# DC_POWER.net
KiCad netlist of a schematic drawn in Altium Designer
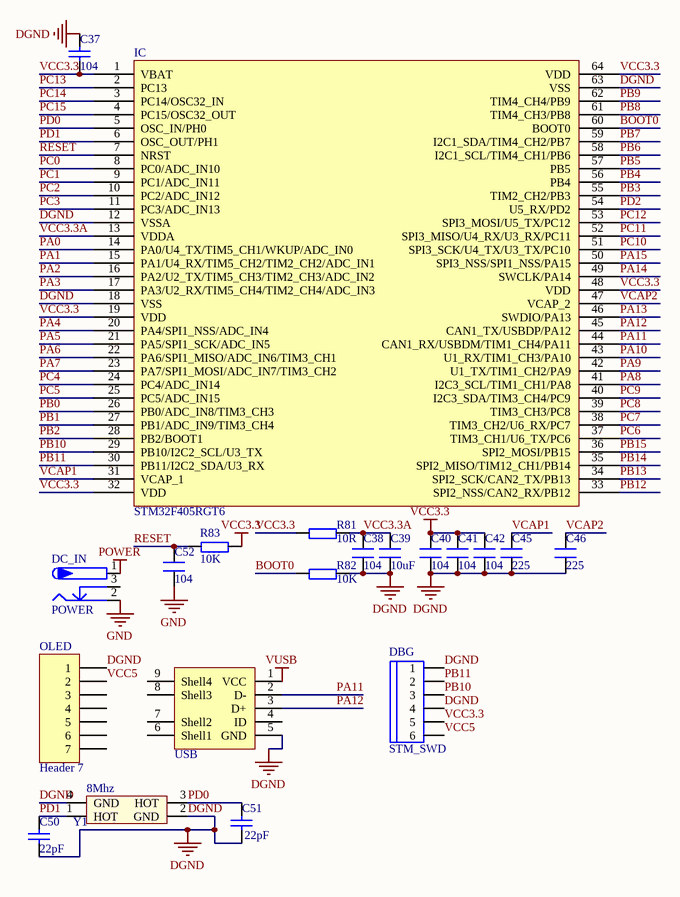
[diagram p0: DC_POWER.SchDoc]

(export (version "E")
  (design (tool "Eeschema 10.0.6"))
  (components
    (comp (ref "C37") (value "104") (footprint "C 0603_L") (libsource (lib "L476") (part "CAP")))
    (comp (ref "C38")
      (value "104")
      (footprint "C 0603_L")
      (libsource (lib "WarShip V3 STM32103封装库") (part "C"))
    )
    (comp (ref "C39")
      (value "10uF")
      (footprint "C 0603_L")
      (libsource (lib "WarShip V3 STM32103封装库") (part "C"))
    )
    (comp (ref "C40")
      (value "104")
      (footprint "C 0603_L")
      (libsource (lib "WarShip V3 STM32103封装库") (part "C"))
    )
    (comp (ref "C41")
      (value "104")
      (footprint "C 0603_L")
      (libsource (lib "WarShip V3 STM32103封装库") (part "C"))
    )
    (comp (ref "C42")
      (value "104")
      (footprint "C 0603_L")
      (libsource (lib "WarShip V3 STM32103封装库") (part "C"))
    )
    (comp (ref "C45")
      (value "225")
      (footprint "C 0603_L")
      (libsource (lib "WarShip V3 STM32103封装库") (part "C"))
    )
    (comp (ref "C46")
      (value "225")
      (footprint "C 0603_L")
      (libsource (lib "WarShip V3 STM32103封装库") (part "C"))
    )
    (comp (ref "C50") (value "22pF") (footprint "C 0603_L") (libsource (lib "L476") (part "CAP")))
    (comp (ref "C51") (value "22pF") (footprint "C 0603_L") (libsource (lib "L476") (part "CAP")))
    (comp (ref "C52")
      (value "104")
      (footprint "C 0603_L")
      (libsource (lib "WarShip V3 STM32103封装库") (part "C"))
    )
    (comp (ref "DBG") (value "STM_SWD") (footprint "SH1.0_6P") (libsource (lib "MiniFly ") (part "HEAD6")))
    (comp (ref "DC_IN")
      (value "POWER")
      (footprint "DC10B")
      (description "低压电源接口")
      (fields (field (name "版权归属") "源创客"))
      (libsource (lib "IMX6UL_ALPHA(底板)_V2.0") (part "P-DC"))
    )
    (comp (ref "IC")
      (value "STM32F405RGT6")
      (footprint "LQFP64 10X10_L")
      (description "Flaah:256/RAM:48/IO:51")
      (libsource (lib "ATKF405 V1.1") (part "STM32F405RGT6"))
    )
    (comp (ref "OLED")
      (value "Header 7")
      (footprint "HDR2.54-M-LI-7P")
      (description "Header, 7-Pin")
      (fields (field (name "PUBLISHER") "Altium Limited"))
      (libsource (lib "Miscellaneous Connectors") (part "Header 7"))
    )
    (comp (ref "R81")
      (value "10R")
      (footprint "R 0603_L")
      (libsource (lib "WarShip V3 STM32103封装库") (part "R"))
    )
    (comp (ref "R82")
      (value "10K")
      (footprint "R 0603_L")
      (libsource (lib "WarShip V3 STM32103封装库") (part "R"))
    )
    (comp (ref "R83")
      (value "10K")
      (footprint "R 0603_L")
      (libsource (lib "WarShip V3 STM32103封装库") (part "R"))
    )
    (comp (ref "USB")
      (value "MICRO-USB")
      (footprint "USB-AB-5S")
      (description "Micro USB 5.9有柱脚长1.25加长针")
      (libsource (lib "Pandora_STM32L4_Board_V2.4") (part "J-MICRO-USB-5S"))
    )
    (comp (ref "Y1")
      (value "8Mhz")
      (footprint "XTAL-3225")
      (description "3225贴片无源晶振")
      (libsource (lib "ALIENTEK_COMPONENT") (part "XTAL_3225"))
    )
  )
  (nets
    (net (code "1") (name "/BOOT0") (class "Default")
      (node (ref "IC") (pin "60") (pinfunction "BOOT0_60") (pintype "passive"))
      (node (ref "R82") (pin "1") (pintype "passive"))
    )
    (net (code "2") (name "/PA0") (class "Default")
      (node (ref "IC") (pin "14") (pinfunction "PA0/U4_TX/TIM5_CH1/WKUP/ADC_IN0_14") (pintype "passive"))
    )
    (net (code "3") (name "/PA1") (class "Default")
      (node (ref "IC") (pin "15") (pinfunction "PA1/U4_RX/TIM5_CH2/TIM2_CH2/ADC_IN1_15") (pintype "passive"))
    )
    (net (code "4") (name "/PA2") (class "Default")
      (node (ref "IC") (pin "16") (pinfunction "PA2/U2_TX/TIM5_CH3/TIM2_CH3/ADC_IN2_16") (pintype "passive"))
    )
    (net (code "5") (name "/PA3") (class "Default")
      (node (ref "IC") (pin "17") (pinfunction "PA3/U2_RX/TIM5_CH4/TIM2_CH4/ADC_IN3_17") (pintype "passive"))
    )
    (net (code "6") (name "/PA4") (class "Default")
      (node (ref "IC") (pin "20") (pinfunction "PA4/SPI1_NSS/ADC_IN4_20") (pintype "passive"))
    )
    (net (code "7") (name "/PA5") (class "Default")
      (node (ref "IC") (pin "21") (pinfunction "PA5/SPI1_SCK/ADC_IN5_21") (pintype "passive"))
    )
    (net (code "8") (name "/PA6") (class "Default")
      (node (ref "IC") (pin "22") (pinfunction "PA6/SPI1_MISO/ADC_IN6/TIM3_CH1_22") (pintype "passive"))
    )
    (net (code "9") (name "/PA7") (class "Default")
      (node (ref "IC") (pin "23") (pinfunction "PA7/SPI1_MOSI/ADC_IN7/TIM3_CH2_23") (pintype "passive"))
    )
    (net (code "10") (name "/PA8") (class "Default")
      (node (ref "IC") (pin "41") (pinfunction "I2C3_SCL/TIM1_CH1/PA8_41") (pintype "passive"))
    )
    (net (code "11") (name "/PA9") (class "Default")
      (node (ref "IC") (pin "42") (pinfunction "U1_TX/TIM1_CH2/PA9_42") (pintype "passive"))
    )
    (net (code "12") (name "/PA10") (class "Default")
      (node (ref "IC") (pin "43") (pinfunction "U1_RX/TIM1_CH3/PA10_43") (pintype "passive"))
    )
    (net (code "13") (name "/PA11") (class "Default")
      (node (ref "IC") (pin "44") (pinfunction "CAN1_RX/USBDM/TIM1_CH4/PA11_44") (pintype "passive"))
      (node (ref "USB") (pin "2") (pinfunction "D-_2") (pintype "passive"))
    )
    (net (code "14") (name "/PA12") (class "Default")
      (node (ref "IC") (pin "45") (pinfunction "CAN1_TX/USBDP/PA12_45") (pintype "passive"))
      (node (ref "USB") (pin "3") (pinfunction "D+_3") (pintype "passive"))
    )
    (net (code "15") (name "/PA13") (class "Default")
      (node (ref "IC") (pin "46") (pinfunction "SWDIO/PA13_46") (pintype "passive"))
    )
    (net (code "16") (name "/PA14") (class "Default")
      (node (ref "IC") (pin "49") (pinfunction "SWCLK/PA14_49") (pintype "passive"))
    )
    (net (code "17") (name "/PA15") (class "Default")
      (node (ref "IC") (pin "50") (pinfunction "SPI3_NSS/SPI1_NSS/PA15_50") (pintype "passive"))
    )
    (net (code "18") (name "/PB0") (class "Default")
      (node (ref "IC") (pin "26") (pinfunction "PB0/ADC_IN8/TIM3_CH3_26") (pintype "passive"))
    )
    (net (code "19") (name "/PB1") (class "Default")
      (node (ref "IC") (pin "27") (pinfunction "PB1/ADC_IN9/TIM3_CH4_27") (pintype "passive"))
    )
    (net (code "20") (name "/PB2") (class "Default")
      (node (ref "IC") (pin "28") (pinfunction "PB2/BOOT1_28") (pintype "passive"))
    )
    (net (code "21") (name "/PB3") (class "Default")
      (node (ref "IC") (pin "55") (pinfunction "TIM2_CH2/PB3_55") (pintype "passive"))
    )
    (net (code "22") (name "/PB4") (class "Default")
      (node (ref "IC") (pin "56") (pinfunction "PB4_56") (pintype "passive"))
    )
    (net (code "23") (name "/PB5") (class "Default")
      (node (ref "IC") (pin "57") (pinfunction "PB5_57") (pintype "passive"))
    )
    (net (code "24") (name "/PB6") (class "Default")
      (node (ref "IC") (pin "58") (pinfunction "I2C1_SCL/TIM4_CH1/PB6_58") (pintype "passive"))
    )
    (net (code "25") (name "/PB7") (class "Default")
      (node (ref "IC") (pin "59") (pinfunction "I2C1_SDA/TIM4_CH2/PB7_59") (pintype "passive"))
    )
    (net (code "26") (name "/PB8") (class "Default")
      (node (ref "IC") (pin "61") (pinfunction "TIM4_CH3/PB8_61") (pintype "passive"))
    )
    (net (code "27") (name "/PB9") (class "Default")
      (node (ref "IC") (pin "62") (pinfunction "TIM4_CH4/PB9_62") (pintype "passive"))
    )
    (net (code "28") (name "/PB10") (class "Default")
      (node (ref "DBG") (pin "3") (pinfunction "3_3") (pintype "passive"))
      (node (ref "IC") (pin "29") (pinfunction "PB10/I2C2_SCL/U3_TX_29") (pintype "passive"))
    )
    (net (code "29") (name "/PB11") (class "Default")
      (node (ref "DBG") (pin "2") (pinfunction "2_2") (pintype "passive"))
      (node (ref "IC") (pin "30") (pinfunction "PB11/I2C2_SDA/U3_RX_30") (pintype "passive"))
    )
    (net (code "30") (name "/PB12") (class "Default")
      (node (ref "IC") (pin "33") (pinfunction "SPI2_NSS/CAN2_RX/PB12_33") (pintype "passive"))
    )
    (net (code "31") (name "/PB13") (class "Default")
      (node (ref "IC") (pin "34") (pinfunction "SPI2_SCK/CAN2_TX/PB13_34") (pintype "passive"))
    )
    (net (code "32") (name "/PB14") (class "Default")
      (node (ref "IC") (pin "35") (pinfunction "SPI2_MISO/TIM12_CH1/PB14_35") (pintype "passive"))
    )
    (net (code "33") (name "/PB15") (class "Default")
      (node (ref "IC") (pin "36") (pinfunction "SPI2_MOSI/PB15_36") (pintype "passive"))
    )
    (net (code "34") (name "/PC0") (class "Default")
      (node (ref "IC") (pin "8") (pinfunction "PC0/ADC_IN10_8") (pintype "passive"))
    )
    (net (code "35") (name "/PC1") (class "Default")
      (node (ref "IC") (pin "9") (pinfunction "PC1/ADC_IN11_9") (pintype "passive"))
    )
    (net (code "36") (name "/PC2") (class "Default")
      (node (ref "IC") (pin "10") (pinfunction "PC2/ADC_IN12_10") (pintype "passive"))
    )
    (net (code "37") (name "/PC3") (class "Default")
      (node (ref "IC") (pin "11") (pinfunction "PC3/ADC_IN13_11") (pintype "passive"))
    )
    (net (code "38") (name "/PC4") (class "Default")
      (node (ref "IC") (pin "24") (pinfunction "PC4/ADC_IN14_24") (pintype "passive"))
    )
    (net (code "39") (name "/PC5") (class "Default")
      (node (ref "IC") (pin "25") (pinfunction "PC5/ADC_IN15_25") (pintype "passive"))
    )
    (net (code "40") (name "/PC6") (class "Default")
      (node (ref "IC") (pin "37") (pinfunction "TIM3_CH1/U6_TX/PC6_37") (pintype "passive"))
    )
    (net (code "41") (name "/PC7") (class "Default")
      (node (ref "IC") (pin "38") (pinfunction "TIM3_CH2/U6_RX/PC7_38") (pintype "passive"))
    )
    (net (code "42") (name "/PC8") (class "Default")
      (node (ref "IC") (pin "39") (pinfunction "TIM3_CH3/PC8_39") (pintype "passive"))
    )
    (net (code "43") (name "/PC9") (class "Default")
      (node (ref "IC") (pin "40") (pinfunction "I2C3_SDA/TIM3_CH4/PC9_40") (pintype "passive"))
    )
    (net (code "44") (name "/PC10") (class "Default")
      (node (ref "IC") (pin "51") (pinfunction "SPI3_SCK/U4_TX/U3_TX/PC10_51") (pintype "passive"))
    )
    (net (code "45") (name "/PC11") (class "Default")
      (node (ref "IC") (pin "52") (pinfunction "SPI3_MISO/U4_RX/U3_RX/PC11_52") (pintype "passive"))
    )
    (net (code "46") (name "/PC12") (class "Default")
      (node (ref "IC") (pin "53") (pinfunction "SPI3_MOSI/U5_TX/PC12_53") (pintype "passive"))
    )
    (net (code "47") (name "/PC13") (class "Default")
      (node (ref "IC") (pin "2") (pinfunction "PC13_2") (pintype "passive"))
    )
    (net (code "48") (name "/PC14") (class "Default")
      (node (ref "IC") (pin "3") (pinfunction "PC14/OSC32_IN_3") (pintype "passive"))
    )
    (net (code "49") (name "/PC15") (class "Default")
      (node (ref "IC") (pin "4") (pinfunction "PC15/OSC32_OUT_4") (pintype "passive"))
    )
    (net (code "50") (name "/PD0") (class "Default")
      (node (ref "C51") (pin "2") (pinfunction "2_2") (pintype "passive"))
      (node (ref "IC") (pin "5") (pinfunction "OSC_IN/PH0_5") (pintype "passive"))
      (node (ref "Y1") (pin "3") (pinfunction "HOT_3") (pintype "passive"))
    )
    (net (code "51") (name "/PD1") (class "Default")
      (node (ref "C50") (pin "2") (pinfunction "2_2") (pintype "passive"))
      (node (ref "IC") (pin "6") (pinfunction "OSC_OUT/PH1_6") (pintype "passive"))
      (node (ref "Y1") (pin "1") (pinfunction "HOT_1") (pintype "passive"))
    )
    (net (code "52") (name "/PD2") (class "Default")
      (node (ref "IC") (pin "54") (pinfunction "U5_RX/PD2_54") (pintype "passive"))
    )
    (net (code "53") (name "/RESET") (class "Default")
      (node (ref "C52") (pin "2") (pintype "passive"))
      (node (ref "IC") (pin "7") (pinfunction "NRST_7") (pintype "passive"))
      (node (ref "R83") (pin "1") (pintype "passive"))
    )
    (net (code "54") (name "/VCAP1") (class "Default")
      (node (ref "C45") (pin "2") (pintype "passive"))
      (node (ref "IC") (pin "31") (pinfunction "VCAP_1_31") (pintype "passive"))
    )
    (net (code "55") (name "/VCAP2") (class "Default")
      (node (ref "C46") (pin "2") (pintype "passive"))
      (node (ref "IC") (pin "47") (pinfunction "VCAP_2_47") (pintype "passive"))
    )
    (net (code "56") (name "/VCC3.3A") (class "Default")
      (node (ref "C38") (pin "2") (pintype "passive"))
      (node (ref "C39") (pin "2") (pintype "passive"))
      (node (ref "IC") (pin "13") (pinfunction "VDDA_13") (pintype "passive"))
      (node (ref "R81") (pin "2") (pintype "passive"))
    )
    (net (code "57") (name "/VCC5") (class "Default")
      (node (ref "DBG") (pin "6") (pinfunction "6_6") (pintype "passive"))
      (node (ref "OLED") (pin "2") (pinfunction "2_2") (pintype "passive"))
    )
    (net (code "58") (name "DGND") (class "Default")
      (node (ref "C37") (pin "1") (pinfunction "1_1") (pintype "passive"))
      (node (ref "C38") (pin "1") (pintype "passive"))
      (node (ref "C39") (pin "1") (pintype "passive"))
      (node (ref "C40") (pin "1") (pintype "passive"))
      (node (ref "C41") (pin "1") (pintype "passive"))
      (node (ref "C42") (pin "1") (pintype "passive"))
      (node (ref "C45") (pin "1") (pintype "passive"))
      (node (ref "C46") (pin "1") (pintype "passive"))
      (node (ref "C50") (pin "1") (pinfunction "1_1") (pintype "passive"))
      (node (ref "C51") (pin "1") (pinfunction "1_1") (pintype "passive"))
      (node (ref "DBG") (pin "1") (pinfunction "1_1") (pintype "passive"))
      (node (ref "DBG") (pin "4") (pinfunction "4_4") (pintype "passive"))
      (node (ref "IC") (pin "12") (pinfunction "VSSA_12") (pintype "passive"))
      (node (ref "IC") (pin "18") (pinfunction "VSS_18") (pintype "passive"))
      (node (ref "IC") (pin "63") (pinfunction "VSS_63") (pintype "passive"))
      (node (ref "OLED") (pin "1") (pinfunction "1_1") (pintype "passive"))
      (node (ref "R82") (pin "2") (pintype "passive"))
      (node (ref "USB") (pin "5") (pinfunction "GND_5") (pintype "passive"))
      (node (ref "Y1") (pin "2") (pinfunction "GND_2") (pintype "passive"))
      (node (ref "Y1") (pin "4") (pinfunction "GND_4") (pintype "passive"))
    )
    (net (code "59") (name "GND") (class "Default")
      (node (ref "C52") (pin "1") (pintype "passive"))
      (node (ref "DC_IN") (pin "2") (pintype "power_in"))
    )
    (net (code "60") (name "POWER") (class "Default") (node (ref "DC_IN") (pin "1") (pintype "power_in")))
    (net (code "61") (name "VCC3.3") (class "Default")
      (node (ref "C37") (pin "2") (pinfunction "2_2") (pintype "passive"))
      (node (ref "C40") (pin "2") (pintype "passive"))
      (node (ref "C41") (pin "2") (pintype "passive"))
      (node (ref "C42") (pin "2") (pintype "passive"))
      (node (ref "DBG") (pin "5") (pinfunction "5_5") (pintype "passive"))
      (node (ref "IC") (pin "1") (pinfunction "VBAT_1") (pintype "passive"))
      (node (ref "IC") (pin "19") (pinfunction "VDD_19") (pintype "passive"))
      (node (ref "IC") (pin "32") (pinfunction "VDD_32") (pintype "passive"))
      (node (ref "IC") (pin "48") (pinfunction "VDD_48") (pintype "passive"))
      (node (ref "IC") (pin "64") (pinfunction "VDD_64") (pintype "passive"))
      (node (ref "R81") (pin "1") (pintype "passive"))
      (node (ref "R83") (pin "2") (pintype "passive"))
    )
    (net (code "62") (name "VUSB") (class "Default")
      (node (ref "USB") (pin "1") (pinfunction "VCC_1") (pintype "passive"))
    )
    (net (code "63") (name "unconnected-(DC_IN-Pad3)") (class "Default")
      (node (ref "DC_IN") (pin "3") (pintype "power_in"))
    )
    (net (code "64") (name "unconnected-(OLED-Pad3)") (class "Default")
      (node (ref "OLED") (pin "3") (pinfunction "3_3") (pintype "passive"))
    )
    (net (code "65") (name "unconnected-(OLED-Pad4)") (class "Default")
      (node (ref "OLED") (pin "4") (pinfunction "4_4") (pintype "passive"))
    )
    (net (code "66") (name "unconnected-(OLED-Pad5)") (class "Default")
      (node (ref "OLED") (pin "5") (pinfunction "5_5") (pintype "passive"))
    )
    (net (code "67") (name "unconnected-(OLED-Pad6)") (class "Default")
      (node (ref "OLED") (pin "6") (pinfunction "6_6") (pintype "passive"))
    )
    (net (code "68") (name "unconnected-(OLED-Pad7)") (class "Default")
      (node (ref "OLED") (pin "7") (pinfunction "7_7") (pintype "passive"))
    )
    (net (code "69") (name "unconnected-(USB-ID-Pad4)") (class "Default")
      (node (ref "USB") (pin "4") (pinfunction "ID_4") (pintype "passive"))
    )
    (net (code "70") (name "unconnected-(USB-Shell1-Pad6)") (class "Default")
      (node (ref "USB") (pin "6") (pinfunction "Shell1_6") (pintype "passive"))
    )
    (net (code "71") (name "unconnected-(USB-Shell2-Pad7)") (class "Default")
      (node (ref "USB") (pin "7") (pinfunction "Shell2_7") (pintype "passive"))
    )
    (net (code "72") (name "unconnected-(USB-Shell3-Pad8)") (class "Default")
      (node (ref "USB") (pin "8") (pinfunction "Shell3_8") (pintype "passive"))
    )
    (net (code "73") (name "unconnected-(USB-Shell4-Pad9)") (class "Default")
      (node (ref "USB") (pin "9") (pinfunction "Shell4_9") (pintype "passive"))
    )
  )
)
